# 4_46.net
KiCad netlist of a schematic drawn in EasyEDA
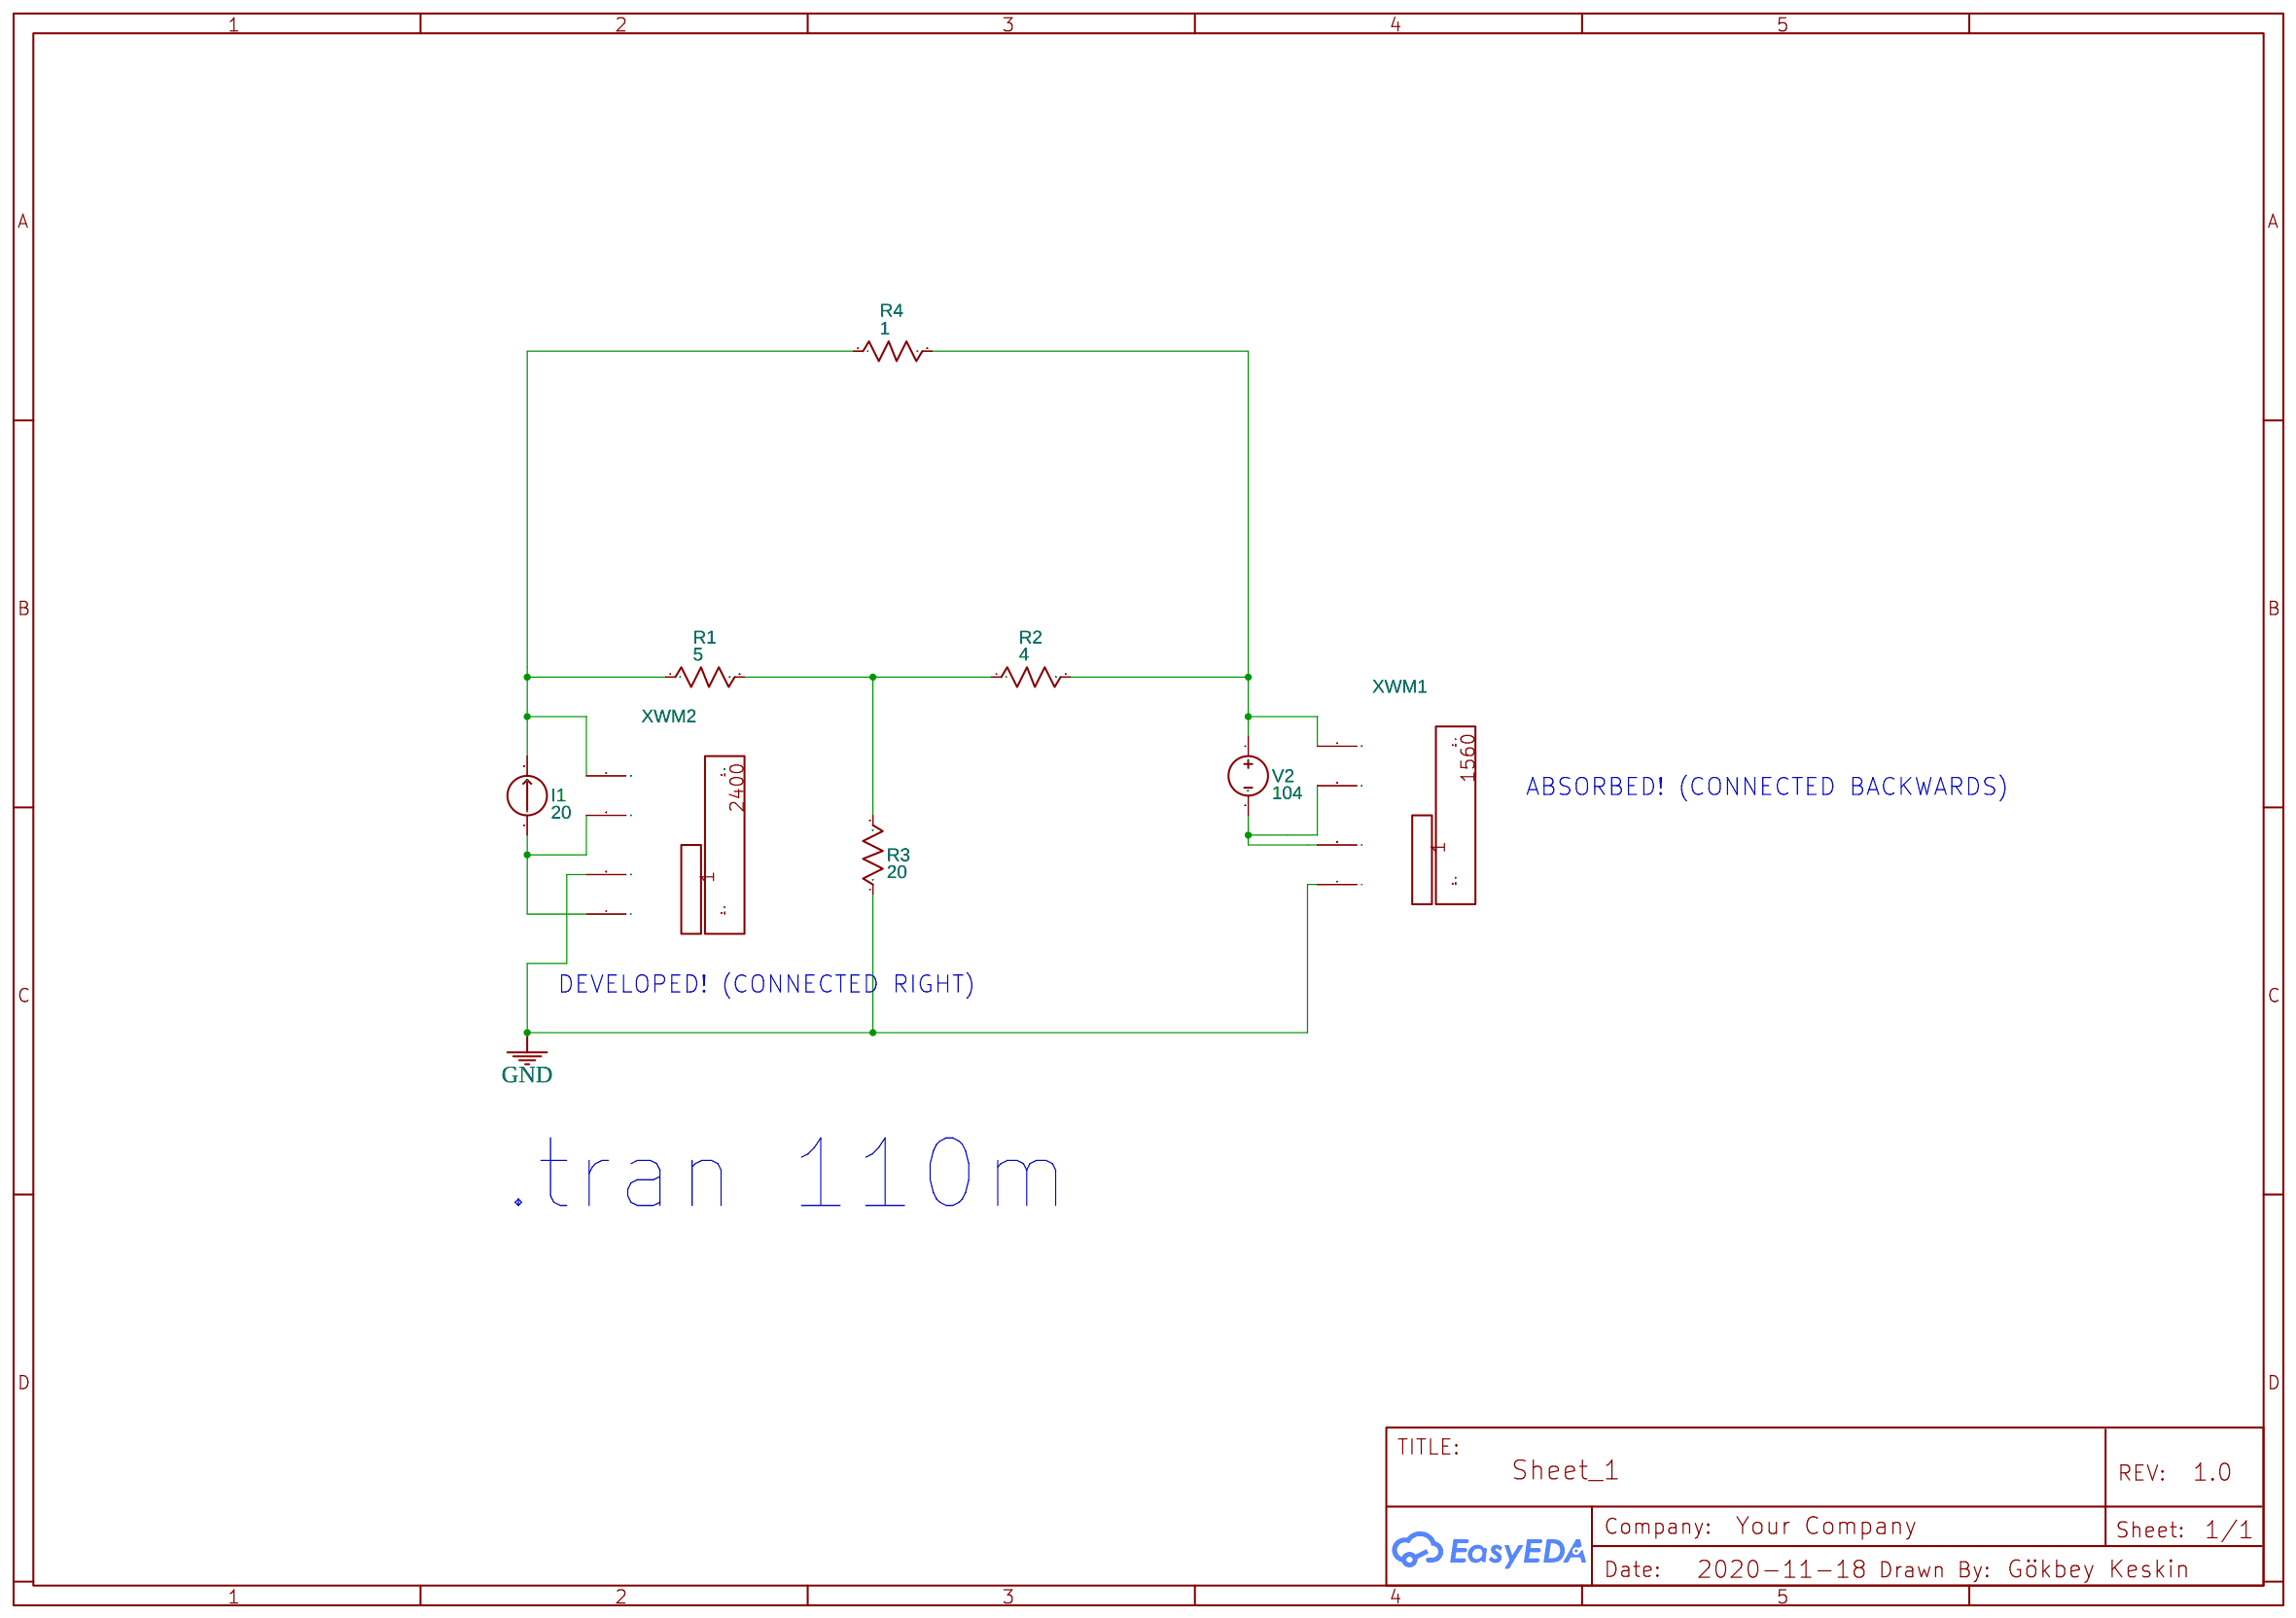
[diagram p0: schematic sheet]

(export (version "E")
  (design (tool "Eeschema 10.0.6"))
  (components
    (comp (ref "I1") (value "20") (libsource (lib "") (part "IDC")))
    (comp (ref "R1") (value "5") (libsource (lib "") (part "Resistor_US")))
    (comp (ref "R2") (value "4") (libsource (lib "") (part "Resistor_US")))
    (comp (ref "R3") (value "20") (libsource (lib "") (part "Resistor_US_1")))
    (comp (ref "R4") (value "1") (libsource (lib "") (part "Resistor_US")))
    (comp (ref "V2") (value "104") (libsource (lib "") (part "VDC")))
    (comp (ref "XWM1") (value "Wattmeter") (libsource (lib "") (part "WATTMETER")))
    (comp (ref "XWM2") (value "Wattmeter") (libsource (lib "") (part "WATTMETER_1")))
  )
  (nets
    (net (code "1") (name "GND") (class "Default")
      (node (ref "R3") (pin "1") (pinfunction "1_1") (pintype "unspecified"))
      (node (ref "XWM1") (pin "4") (pinfunction "I-_4") (pintype "unspecified"))
      (node (ref "XWM2") (pin "3") (pinfunction "I+_3") (pintype "unspecified"))
    )
    (net (code "2") (name "Net-(R1-Pad2)") (class "Default")
      (node (ref "R1") (pin "2") (pinfunction "2_2") (pintype "unspecified"))
      (node (ref "R2") (pin "1") (pinfunction "1_1") (pintype "unspecified"))
      (node (ref "R3") (pin "2") (pinfunction "2_2") (pintype "unspecified"))
    )
    (net (code "3") (name "Net-(XWM1-I+)") (class "Default")
      (node (ref "V2") (pin "2") (pinfunction "2_2") (pintype "unspecified"))
      (node (ref "XWM1") (pin "2") (pinfunction "V-_2") (pintype "unspecified"))
      (node (ref "XWM1") (pin "3") (pinfunction "I+_3") (pintype "unspecified"))
    )
    (net (code "4") (name "Net-(XWM1-V+)") (class "Default")
      (node (ref "R2") (pin "2") (pinfunction "2_2") (pintype "unspecified"))
      (node (ref "R4") (pin "2") (pinfunction "2_2") (pintype "unspecified"))
      (node (ref "V2") (pin "1") (pinfunction "1_1") (pintype "unspecified"))
      (node (ref "XWM1") (pin "1") (pinfunction "V+_1") (pintype "unspecified"))
    )
    (net (code "5") (name "Net-(XWM2-I-)") (class "Default")
      (node (ref "I1") (pin "1") (pinfunction "1_1") (pintype "unspecified"))
      (node (ref "XWM2") (pin "2") (pinfunction "V-_2") (pintype "unspecified"))
      (node (ref "XWM2") (pin "4") (pinfunction "I-_4") (pintype "unspecified"))
    )
    (net (code "6") (name "Net-(XWM2-V+)") (class "Default")
      (node (ref "I1") (pin "2") (pinfunction "2_2") (pintype "unspecified"))
      (node (ref "R1") (pin "1") (pinfunction "1_1") (pintype "unspecified"))
      (node (ref "R4") (pin "1") (pinfunction "1_1") (pintype "unspecified"))
      (node (ref "XWM2") (pin "1") (pinfunction "V+_1") (pintype "unspecified"))
    )
    (net (code "7") (name "unconnected-(XWM1-PadP)") (class "Default")
      (node (ref "XWM1") (pin "P") (pinfunction "P_P") (pintype "unspecified"))
    )
    (net (code "8") (name "unconnected-(XWM1-PadPF)") (class "Default")
      (node (ref "XWM1") (pin "PF") (pinfunction "PF_PF") (pintype "unspecified"))
    )
    (net (code "9") (name "unconnected-(XWM2-PadP)") (class "Default")
      (node (ref "XWM2") (pin "P") (pinfunction "P_P") (pintype "unspecified"))
    )
    (net (code "10") (name "unconnected-(XWM2-PadPF)") (class "Default")
      (node (ref "XWM2") (pin "PF") (pinfunction "PF_PF") (pintype "unspecified"))
    )
  )
)
